# zdroj12v3v7.net
KiCad netlist of a schematic drawn in EAGLE
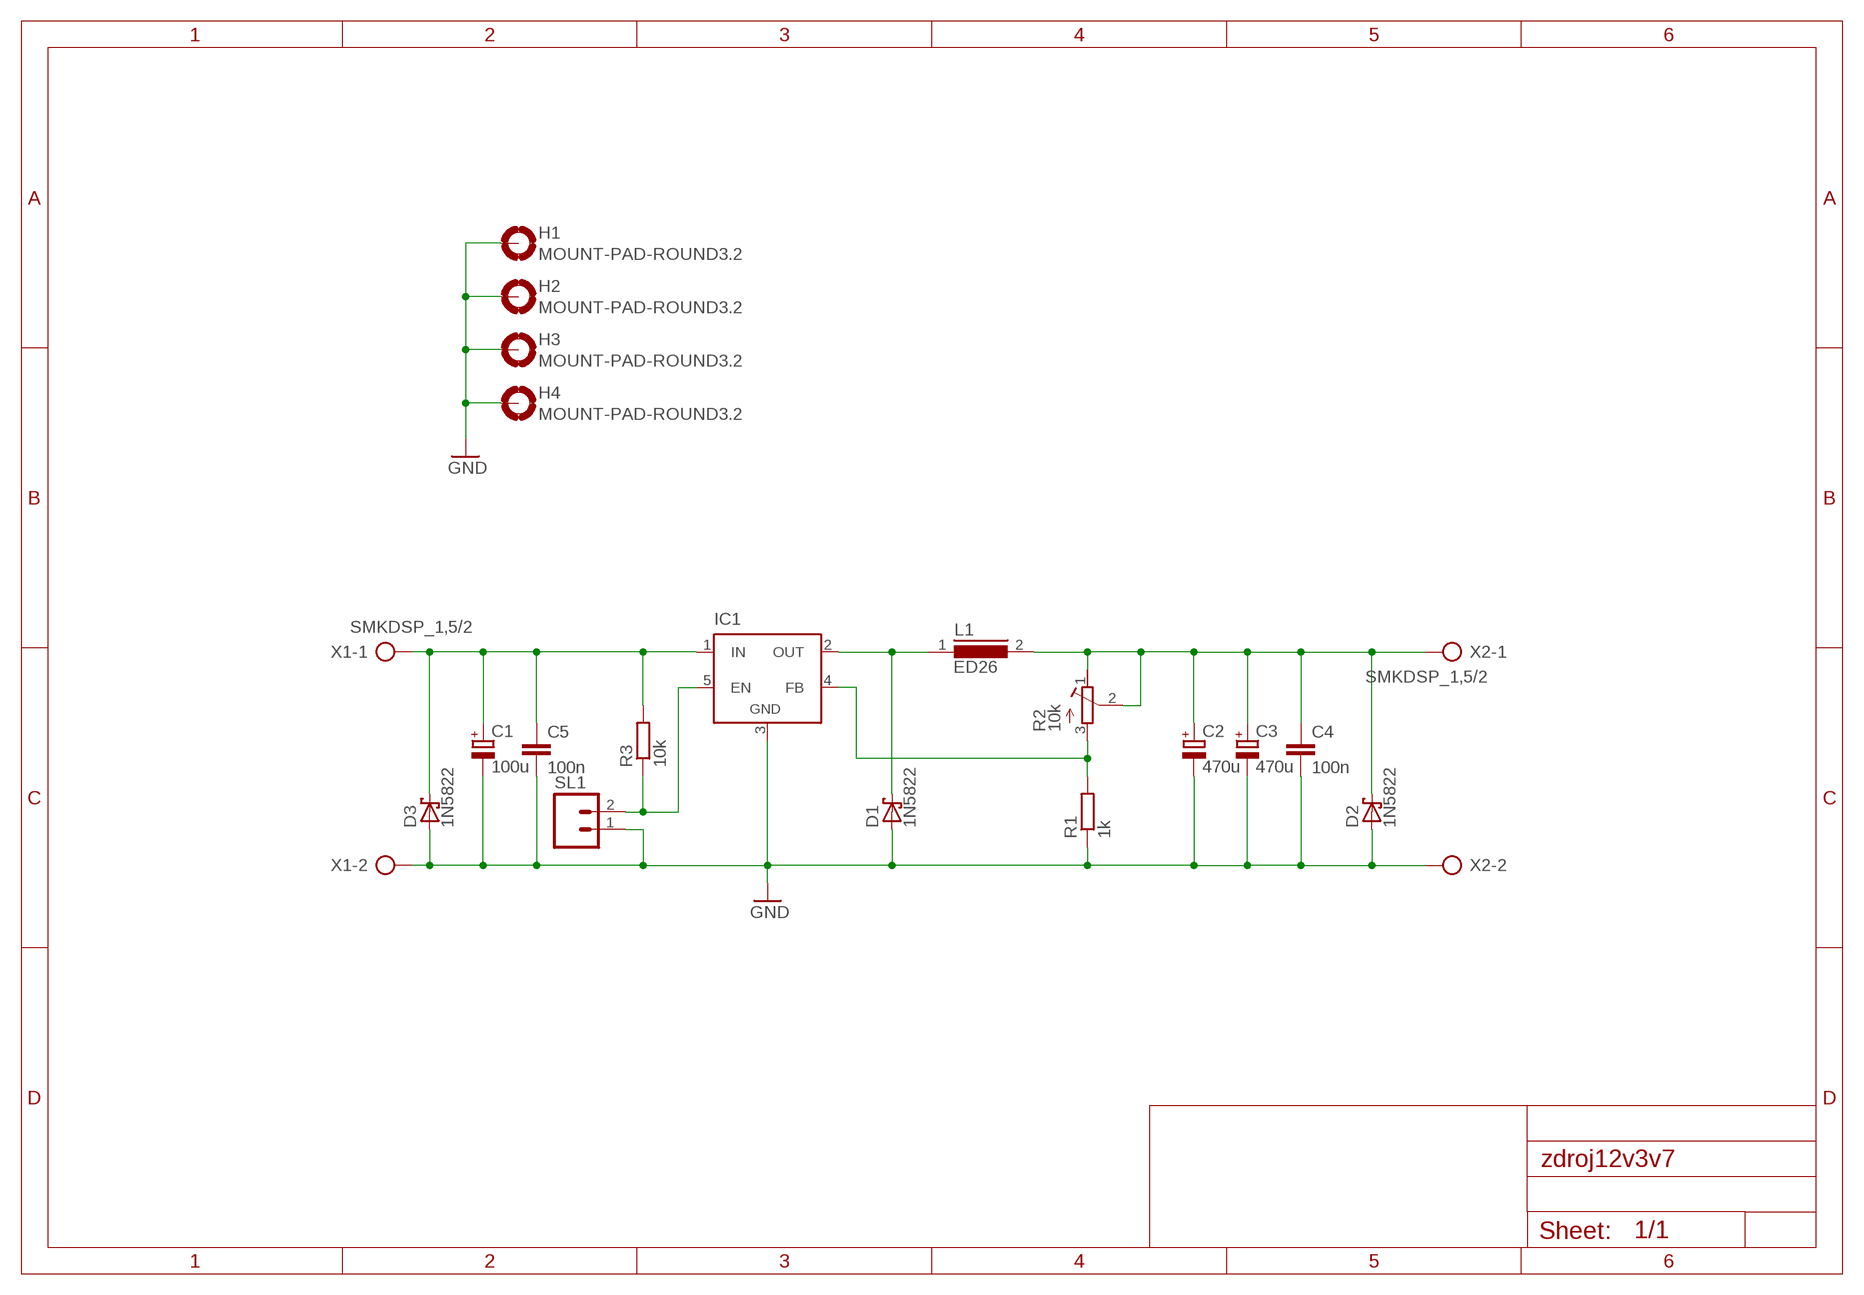
[diagram p0: schematic, sheet 1]

(export (version "E")
  (design (tool "Eeschema 10.0.6"))
  (components
    (comp (ref "C1")
      (value "100u")
      (footprint "eagle-import:E5-8,5")
      (libsource (lib "eagle-import") (part "CPOL-EUE5-8.5"))
    )
    (comp (ref "C2")
      (value "470u")
      (footprint "eagle-import:E5-10,5")
      (libsource (lib "eagle-import") (part "CPOL-EUE5-10.5"))
    )
    (comp (ref "C3")
      (value "470u")
      (footprint "eagle-import:E5-10,5")
      (libsource (lib "eagle-import") (part "CPOL-EUE5-10.5"))
    )
    (comp (ref "C4")
      (value "100n")
      (footprint "eagle-import:C050-035X075")
      (libsource (lib "eagle-import") (part "C-EU050-035X075"))
    )
    (comp (ref "C5")
      (value "100n")
      (footprint "eagle-import:C050-035X075")
      (libsource (lib "eagle-import") (part "C-EU050-035X075"))
    )
    (comp (ref "D1")
      (value "1N5822")
      (footprint "eagle-import:DO201T15")
      (libsource (lib "eagle-import") (part "SCHOTTKY-DIODEDO201T15"))
    )
    (comp (ref "D2")
      (value "1N5822")
      (footprint "eagle-import:DO201T15")
      (libsource (lib "eagle-import") (part "SCHOTTKY-DIODEDO201T15"))
    )
    (comp (ref "D3")
      (value "1N5822")
      (footprint "eagle-import:DO201T15")
      (libsource (lib "eagle-import") (part "SCHOTTKY-DIODEDO201T15"))
    )
    (comp (ref "H1")
      (value "MOUNT-PAD-ROUND3.2")
      (footprint "eagle-import:3,2-PAD")
      (libsource (lib "eagle-import") (part "MOUNT-PAD-ROUND3.2"))
    )
    (comp (ref "H2")
      (value "MOUNT-PAD-ROUND3.2")
      (footprint "eagle-import:3,2-PAD")
      (libsource (lib "eagle-import") (part "MOUNT-PAD-ROUND3.2"))
    )
    (comp (ref "H3")
      (value "MOUNT-PAD-ROUND3.2")
      (footprint "eagle-import:3,2-PAD")
      (libsource (lib "eagle-import") (part "MOUNT-PAD-ROUND3.2"))
    )
    (comp (ref "H4")
      (value "MOUNT-PAD-ROUND3.2")
      (footprint "eagle-import:3,2-PAD")
      (libsource (lib "eagle-import") (part "MOUNT-PAD-ROUND3.2"))
    )
    (comp (ref "IC1")
      (value "LM2596TH")
      (footprint "eagle-import:TO220-52")
      (libsource (lib "eagle-import") (part "LM2596TH"))
    )
    (comp (ref "L1")
      (value "ED26")
      (footprint "eagle-import:ED26")
      (libsource (lib "eagle-import") (part "ED26"))
    )
    (comp (ref "R1")
      (value "1k")
      (footprint "eagle-import:0207_10")
      (libsource (lib "eagle-import") (part "R-EU_0207/10"))
    )
    (comp (ref "R2")
      (value "10k")
      (footprint "eagle-import:RTRIM3006P")
      (libsource (lib "eagle-import") (part "R-TRIMM3006P"))
    )
    (comp (ref "R3")
      (value "10k")
      (footprint "eagle-import:0207_10")
      (libsource (lib "eagle-import") (part "R-EU_0207/10"))
    )
    (comp (ref "SL1")
      (value "M02")
      (footprint "eagle-import:02P")
      (libsource (lib "eagle-import") (part "M02"))
    )
    (comp (ref "X1")
      (value "SMKDSP_1,5/2")
      (footprint "eagle-import:SMKDSP_1,5_2")
      (fields (field (name "MF") "FARNELL") (field (name "MPN") "1733570"))
      (libsource (lib "eagle-import") (part "SMKDSP_1,5/2"))
    )
    (comp (ref "X2")
      (value "SMKDSP_1,5/2")
      (footprint "eagle-import:SMKDSP_1,5_2")
      (fields (field (name "MF") "FARNELL") (field (name "MPN") "1733570"))
      (libsource (lib "eagle-import") (part "SMKDSP_1,5/2"))
    )
  )
  (nets
    (net (code "1") (name "GND") (class "Default")
      (node (ref "C1") (pin "-") (pinfunction "-_-") (pintype "passive"))
      (node (ref "C2") (pin "-") (pinfunction "-_-") (pintype "passive"))
      (node (ref "C3") (pin "-") (pinfunction "-_-") (pintype "passive"))
      (node (ref "C4") (pin "2") (pinfunction "2_2") (pintype "passive"))
      (node (ref "C5") (pin "2") (pinfunction "2_2") (pintype "passive"))
      (node (ref "D1") (pin "A") (pinfunction "A_A") (pintype "passive"))
      (node (ref "D2") (pin "A") (pinfunction "A_A") (pintype "passive"))
      (node (ref "D3") (pin "A") (pinfunction "A_A") (pintype "passive"))
      (node (ref "H1") (pin "B3,2") (pinfunction "MOUNT_B3,2") (pintype "passive"))
      (node (ref "H2") (pin "B3,2") (pinfunction "MOUNT_B3,2") (pintype "passive"))
      (node (ref "H3") (pin "B3,2") (pinfunction "MOUNT_B3,2") (pintype "passive"))
      (node (ref "H4") (pin "B3,2") (pinfunction "MOUNT_B3,2") (pintype "passive"))
      (node (ref "IC1") (pin "3") (pinfunction "GND_3") (pintype "power_in"))
      (node (ref "R1") (pin "1") (pinfunction "1_1") (pintype "passive"))
      (node (ref "SL1") (pin "1") (pinfunction "1_1") (pintype "passive"))
      (node (ref "X1") (pin "2") (pinfunction "KL_2") (pintype "passive"))
      (node (ref "X2") (pin "2") (pinfunction "KL_2") (pintype "passive"))
    )
    (net (code "2") (name "Net-(IC1-EN)") (class "Default")
      (node (ref "IC1") (pin "5") (pinfunction "EN_5") (pintype "input"))
      (node (ref "R3") (pin "1") (pinfunction "1_1") (pintype "passive"))
      (node (ref "SL1") (pin "2") (pinfunction "2_2") (pintype "passive"))
    )
    (net (code "3") (name "Net-(IC1-FB)") (class "Default")
      (node (ref "IC1") (pin "4") (pinfunction "FB_4") (pintype "input"))
      (node (ref "R1") (pin "2") (pinfunction "2_2") (pintype "passive"))
      (node (ref "R2") (pin "3") (pinfunction "A_3") (pintype "passive"))
    )
    (net (code "4") (name "Net-(IC1-IN)") (class "Default")
      (node (ref "C1") (pin "+") (pinfunction "+_+") (pintype "passive"))
      (node (ref "C5") (pin "1") (pinfunction "1_1") (pintype "passive"))
      (node (ref "D3") (pin "C") (pinfunction "C_C") (pintype "passive"))
      (node (ref "IC1") (pin "1") (pinfunction "IN_1") (pintype "input"))
      (node (ref "R3") (pin "2") (pinfunction "2_2") (pintype "passive"))
      (node (ref "X1") (pin "1") (pinfunction "KL_1") (pintype "passive"))
    )
    (net (code "5") (name "Net-(IC1-OUT)") (class "Default")
      (node (ref "D1") (pin "C") (pinfunction "C_C") (pintype "passive"))
      (node (ref "IC1") (pin "2") (pinfunction "OUT_2") (pintype "output"))
      (node (ref "L1") (pin "1") (pinfunction "1_1") (pintype "passive"))
    )
    (net (code "6") (name "Net-(R2-E)") (class "Default")
      (node (ref "C2") (pin "+") (pinfunction "+_+") (pintype "passive"))
      (node (ref "C3") (pin "+") (pinfunction "+_+") (pintype "passive"))
      (node (ref "C4") (pin "1") (pinfunction "1_1") (pintype "passive"))
      (node (ref "D2") (pin "C") (pinfunction "C_C") (pintype "passive"))
      (node (ref "L1") (pin "2") (pinfunction "2_2") (pintype "passive"))
      (node (ref "R2") (pin "1") (pinfunction "E_1") (pintype "passive"))
      (node (ref "R2") (pin "2") (pinfunction "S_2") (pintype "passive"))
      (node (ref "X2") (pin "1") (pinfunction "KL_1") (pintype "passive"))
    )
  )
)
